# 2_waffling60-SI_matrix.net
KiCad netlist of a schematic drawn in Altium Designer
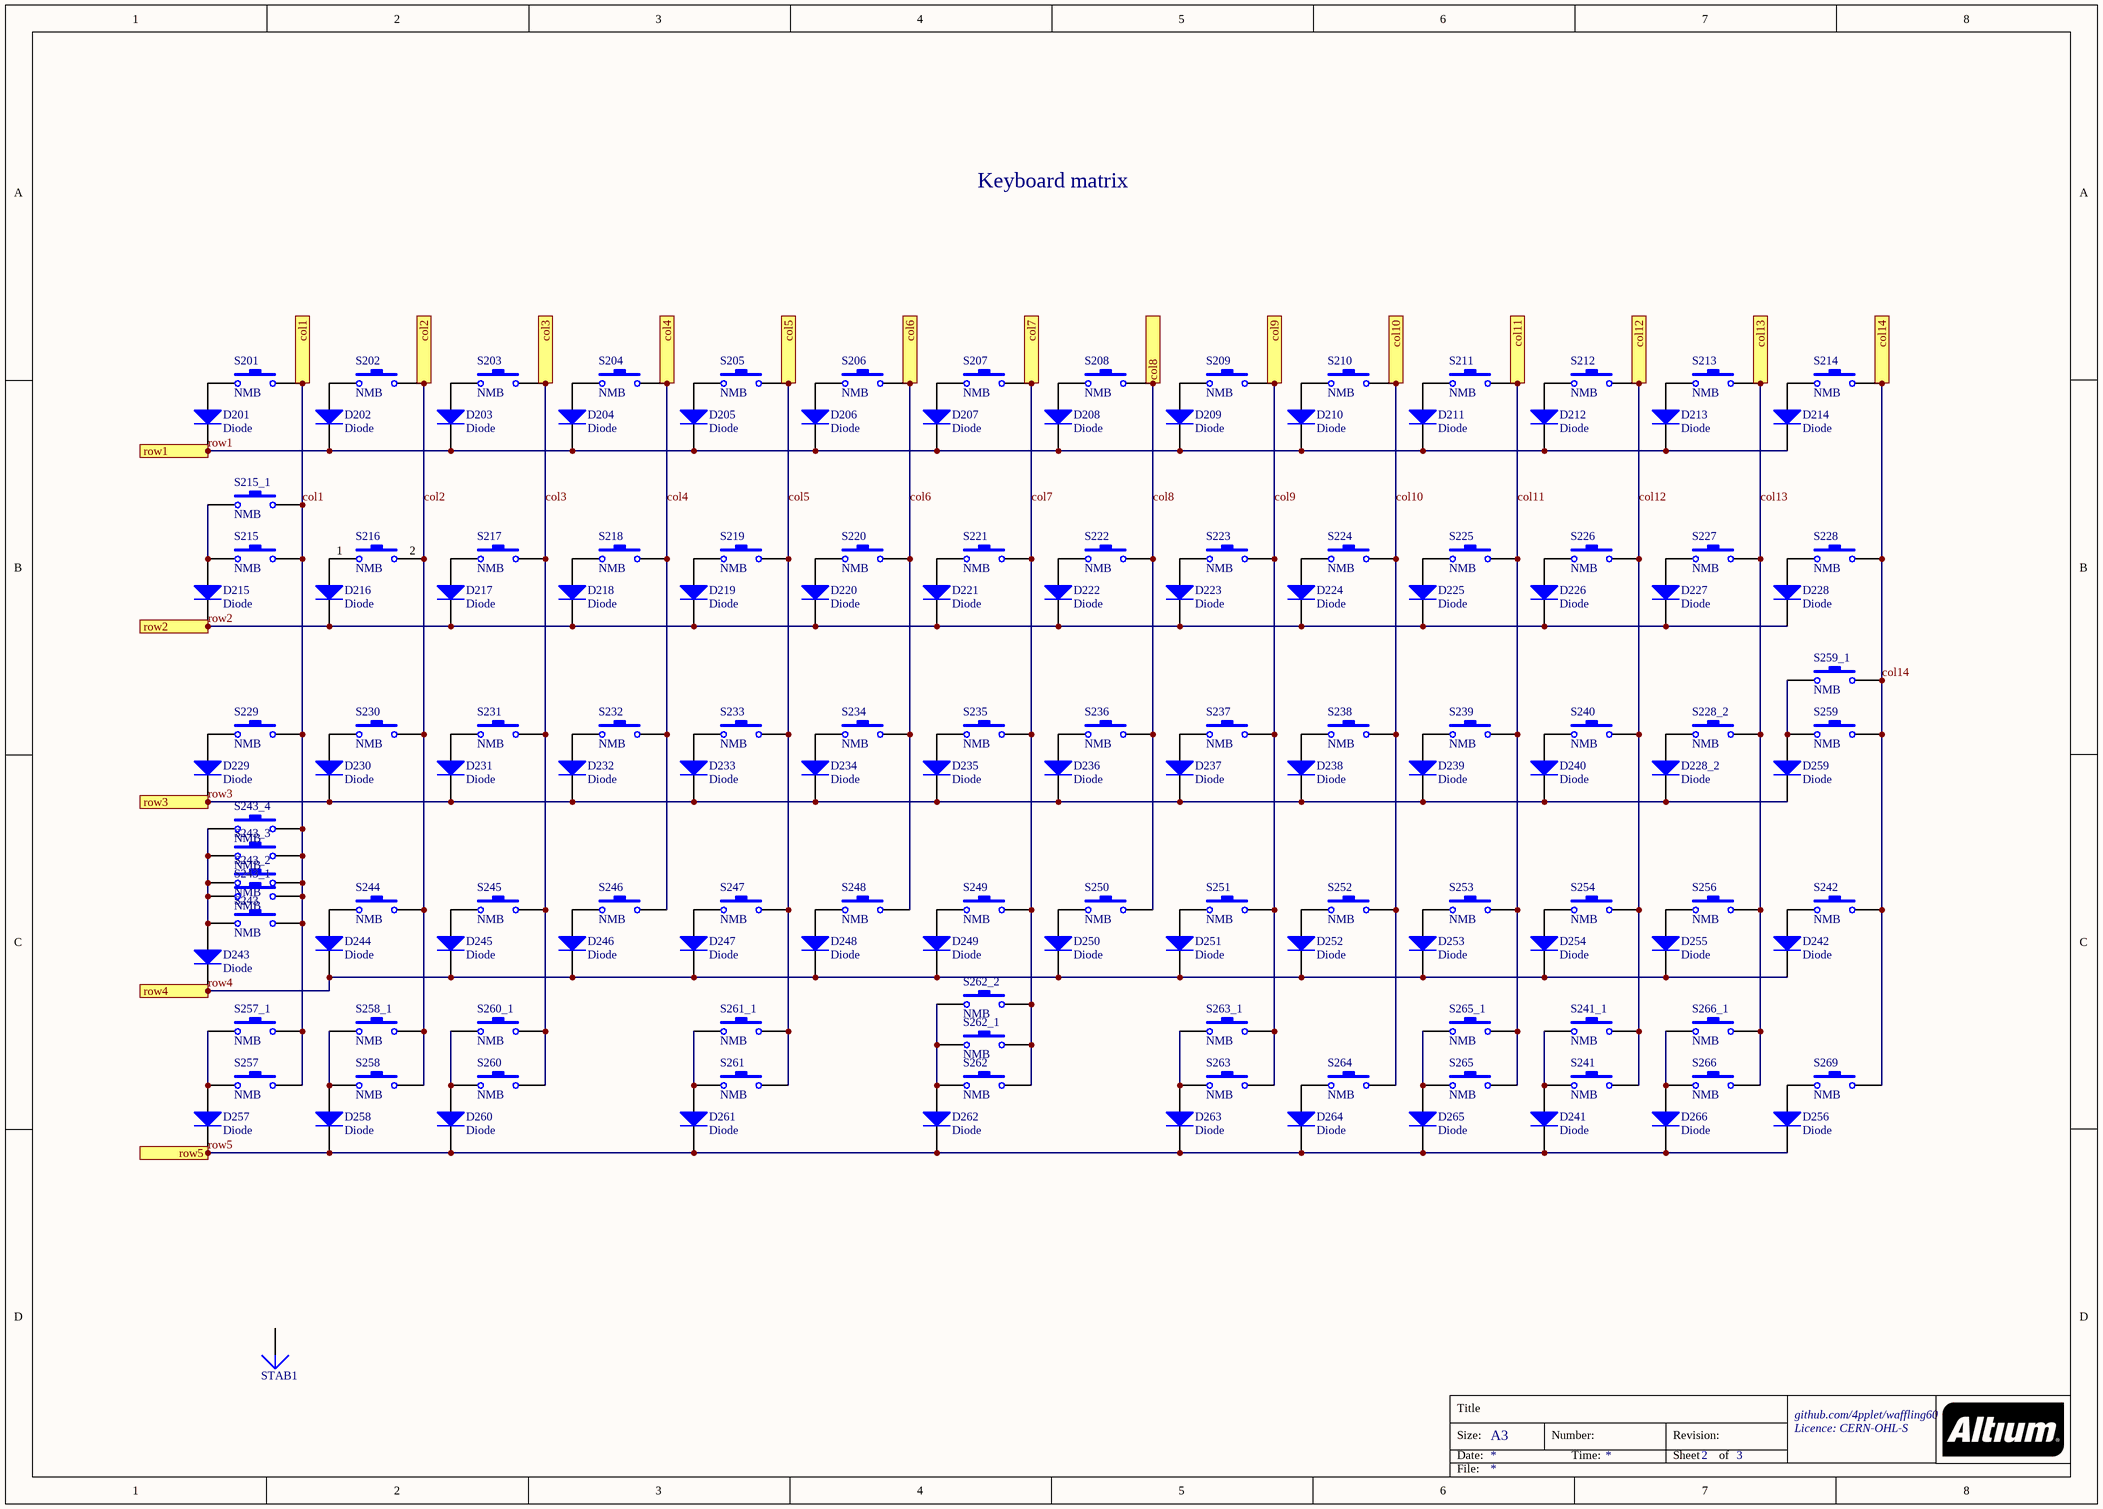
[diagram p0: 2_waffling60-SI_matrix.SchDoc]

(export (version "E")
  (design (tool "Eeschema 10.0.6"))
  (components
    (comp (ref "D201")
      (value "Diode")
      (footprint "SOD-123")
      (description "Default Diode")
      (fields (field (name "LCSC PART #") "C81598") (field (name "MRF.PART") "1N4148W"))
      (libsource (lib "Miscellaneous Devices") (part "Diode"))
    )
    (comp (ref "D202")
      (value "Diode")
      (footprint "SOD-123")
      (description "Default Diode")
      (fields (field (name "LCSC PART #") "C81598") (field (name "MRF.PART") "1N4148W"))
      (libsource (lib "Miscellaneous Devices") (part "Diode"))
    )
    (comp (ref "D203")
      (value "Diode")
      (footprint "SOD-123")
      (description "Default Diode")
      (fields (field (name "LCSC PART #") "C81598") (field (name "MRF.PART") "1N4148W"))
      (libsource (lib "Miscellaneous Devices") (part "Diode"))
    )
    (comp (ref "D204")
      (value "Diode")
      (footprint "SOD-123")
      (description "Default Diode")
      (fields (field (name "LCSC PART #") "C81598") (field (name "MRF.PART") "1N4148W"))
      (libsource (lib "Miscellaneous Devices") (part "Diode"))
    )
    (comp (ref "D205")
      (value "Diode")
      (footprint "SOD-123")
      (description "Default Diode")
      (fields (field (name "LCSC PART #") "C81598") (field (name "MRF.PART") "1N4148W"))
      (libsource (lib "Miscellaneous Devices") (part "Diode"))
    )
    (comp (ref "D206")
      (value "Diode")
      (footprint "SOD-123")
      (description "Default Diode")
      (fields (field (name "LCSC PART #") "C81598") (field (name "MRF.PART") "1N4148W"))
      (libsource (lib "Miscellaneous Devices") (part "Diode"))
    )
    (comp (ref "D207")
      (value "Diode")
      (footprint "SOD-123")
      (description "Default Diode")
      (fields (field (name "LCSC PART #") "C81598") (field (name "MRF.PART") "1N4148W"))
      (libsource (lib "Miscellaneous Devices") (part "Diode"))
    )
    (comp (ref "D208")
      (value "Diode")
      (footprint "SOD-123")
      (description "Default Diode")
      (fields (field (name "LCSC PART #") "C81598") (field (name "MRF.PART") "1N4148W"))
      (libsource (lib "Miscellaneous Devices") (part "Diode"))
    )
    (comp (ref "D209")
      (value "Diode")
      (footprint "SOD-123")
      (description "Default Diode")
      (fields (field (name "LCSC PART #") "C81598") (field (name "MRF.PART") "1N4148W"))
      (libsource (lib "Miscellaneous Devices") (part "Diode"))
    )
    (comp (ref "D210")
      (value "Diode")
      (footprint "SOD-123")
      (description "Default Diode")
      (fields (field (name "LCSC PART #") "C81598") (field (name "MRF.PART") "1N4148W"))
      (libsource (lib "Miscellaneous Devices") (part "Diode"))
    )
    (comp (ref "D211")
      (value "Diode")
      (footprint "SOD-123")
      (description "Default Diode")
      (fields (field (name "LCSC PART #") "C81598") (field (name "MRF.PART") "1N4148W"))
      (libsource (lib "Miscellaneous Devices") (part "Diode"))
    )
    (comp (ref "D212")
      (value "Diode")
      (footprint "SOD-123")
      (description "Default Diode")
      (fields (field (name "LCSC PART #") "C81598") (field (name "MRF.PART") "1N4148W"))
      (libsource (lib "Miscellaneous Devices") (part "Diode"))
    )
    (comp (ref "D213")
      (value "Diode")
      (footprint "SOD-123")
      (description "Default Diode")
      (fields (field (name "LCSC PART #") "C81598") (field (name "MRF.PART") "1N4148W"))
      (libsource (lib "Miscellaneous Devices") (part "Diode"))
    )
    (comp (ref "D214")
      (value "Diode")
      (footprint "SOD-123")
      (description "Default Diode")
      (fields (field (name "LCSC PART #") "C81598") (field (name "MRF.PART") "1N4148W"))
      (libsource (lib "Miscellaneous Devices") (part "Diode"))
    )
    (comp (ref "D215")
      (value "Diode")
      (footprint "SOD-123")
      (description "Default Diode")
      (fields (field (name "LCSC PART #") "C81598") (field (name "MRF.PART") "1N4148W"))
      (libsource (lib "Miscellaneous Devices") (part "Diode"))
    )
    (comp (ref "D216")
      (value "Diode")
      (footprint "SOD-123")
      (description "Default Diode")
      (fields (field (name "LCSC PART #") "C81598") (field (name "MRF.PART") "1N4148W"))
      (libsource (lib "Miscellaneous Devices") (part "Diode"))
    )
    (comp (ref "D217")
      (value "Diode")
      (footprint "SOD-123")
      (description "Default Diode")
      (fields (field (name "LCSC PART #") "C81598") (field (name "MRF.PART") "1N4148W"))
      (libsource (lib "Miscellaneous Devices") (part "Diode"))
    )
    (comp (ref "D218")
      (value "Diode")
      (footprint "SOD-123")
      (description "Default Diode")
      (fields (field (name "LCSC PART #") "C81598") (field (name "MRF.PART") "1N4148W"))
      (libsource (lib "Miscellaneous Devices") (part "Diode"))
    )
    (comp (ref "D219")
      (value "Diode")
      (footprint "SOD-123")
      (description "Default Diode")
      (fields (field (name "LCSC PART #") "C81598") (field (name "MRF.PART") "1N4148W"))
      (libsource (lib "Miscellaneous Devices") (part "Diode"))
    )
    (comp (ref "D220")
      (value "Diode")
      (footprint "SOD-123")
      (description "Default Diode")
      (fields (field (name "LCSC PART #") "C81598") (field (name "MRF.PART") "1N4148W"))
      (libsource (lib "Miscellaneous Devices") (part "Diode"))
    )
    (comp (ref "D221")
      (value "Diode")
      (footprint "SOD-123")
      (description "Default Diode")
      (fields (field (name "LCSC PART #") "C81598") (field (name "MRF.PART") "1N4148W"))
      (libsource (lib "Miscellaneous Devices") (part "Diode"))
    )
    (comp (ref "D222")
      (value "Diode")
      (footprint "SOD-123")
      (description "Default Diode")
      (fields (field (name "LCSC PART #") "C81598") (field (name "MRF.PART") "1N4148W"))
      (libsource (lib "Miscellaneous Devices") (part "Diode"))
    )
    (comp (ref "D223")
      (value "Diode")
      (footprint "SOD-123")
      (description "Default Diode")
      (fields (field (name "LCSC PART #") "C81598") (field (name "MRF.PART") "1N4148W"))
      (libsource (lib "Miscellaneous Devices") (part "Diode"))
    )
    (comp (ref "D224")
      (value "Diode")
      (footprint "SOD-123")
      (description "Default Diode")
      (fields (field (name "LCSC PART #") "C81598") (field (name "MRF.PART") "1N4148W"))
      (libsource (lib "Miscellaneous Devices") (part "Diode"))
    )
    (comp (ref "D225")
      (value "Diode")
      (footprint "SOD-123")
      (description "Default Diode")
      (fields (field (name "LCSC PART #") "C81598") (field (name "MRF.PART") "1N4148W"))
      (libsource (lib "Miscellaneous Devices") (part "Diode"))
    )
    (comp (ref "D226")
      (value "Diode")
      (footprint "SOD-123")
      (description "Default Diode")
      (fields (field (name "LCSC PART #") "C81598") (field (name "MRF.PART") "1N4148W"))
      (libsource (lib "Miscellaneous Devices") (part "Diode"))
    )
    (comp (ref "D227")
      (value "Diode")
      (footprint "SOD-123")
      (description "Default Diode")
      (fields (field (name "LCSC PART #") "C81598") (field (name "MRF.PART") "1N4148W"))
      (libsource (lib "Miscellaneous Devices") (part "Diode"))
    )
    (comp (ref "D228")
      (value "Diode")
      (footprint "SOD-123")
      (description "Default Diode")
      (fields (field (name "LCSC PART #") "C81598") (field (name "MRF.PART") "1N4148W"))
      (libsource (lib "Miscellaneous Devices") (part "Diode"))
    )
    (comp (ref "D228_2")
      (value "Diode")
      (footprint "SOD-123")
      (description "Default Diode")
      (fields (field (name "LCSC PART #") "C81598") (field (name "MRF.PART") "1N4148W"))
      (libsource (lib "Miscellaneous Devices") (part "Diode"))
    )
    (comp (ref "D229")
      (value "Diode")
      (footprint "SOD-123")
      (description "Default Diode")
      (fields (field (name "LCSC PART #") "C81598") (field (name "MRF.PART") "1N4148W"))
      (libsource (lib "Miscellaneous Devices") (part "Diode"))
    )
    (comp (ref "D230")
      (value "Diode")
      (footprint "SOD-123")
      (description "Default Diode")
      (fields (field (name "LCSC PART #") "C81598") (field (name "MRF.PART") "1N4148W"))
      (libsource (lib "Miscellaneous Devices") (part "Diode"))
    )
    (comp (ref "D231")
      (value "Diode")
      (footprint "SOD-123")
      (description "Default Diode")
      (fields (field (name "LCSC PART #") "C81598") (field (name "MRF.PART") "1N4148W"))
      (libsource (lib "Miscellaneous Devices") (part "Diode"))
    )
    (comp (ref "D232")
      (value "Diode")
      (footprint "SOD-123")
      (description "Default Diode")
      (fields (field (name "LCSC PART #") "C81598") (field (name "MRF.PART") "1N4148W"))
      (libsource (lib "Miscellaneous Devices") (part "Diode"))
    )
    (comp (ref "D233")
      (value "Diode")
      (footprint "SOD-123")
      (description "Default Diode")
      (fields (field (name "LCSC PART #") "C81598") (field (name "MRF.PART") "1N4148W"))
      (libsource (lib "Miscellaneous Devices") (part "Diode"))
    )
    (comp (ref "D234")
      (value "Diode")
      (footprint "SOD-123")
      (description "Default Diode")
      (fields (field (name "LCSC PART #") "C81598") (field (name "MRF.PART") "1N4148W"))
      (libsource (lib "Miscellaneous Devices") (part "Diode"))
    )
    (comp (ref "D235")
      (value "Diode")
      (footprint "SOD-123")
      (description "Default Diode")
      (fields (field (name "LCSC PART #") "C81598") (field (name "MRF.PART") "1N4148W"))
      (libsource (lib "Miscellaneous Devices") (part "Diode"))
    )
    (comp (ref "D236")
      (value "Diode")
      (footprint "SOD-123")
      (description "Default Diode")
      (fields (field (name "LCSC PART #") "C81598") (field (name "MRF.PART") "1N4148W"))
      (libsource (lib "Miscellaneous Devices") (part "Diode"))
    )
    (comp (ref "D237")
      (value "Diode")
      (footprint "SOD-123")
      (description "Default Diode")
      (fields (field (name "LCSC PART #") "C81598") (field (name "MRF.PART") "1N4148W"))
      (libsource (lib "Miscellaneous Devices") (part "Diode"))
    )
    (comp (ref "D238")
      (value "Diode")
      (footprint "SOD-123")
      (description "Default Diode")
      (fields (field (name "LCSC PART #") "C81598") (field (name "MRF.PART") "1N4148W"))
      (libsource (lib "Miscellaneous Devices") (part "Diode"))
    )
    (comp (ref "D239")
      (value "Diode")
      (footprint "SOD-123")
      (description "Default Diode")
      (fields (field (name "LCSC PART #") "C81598") (field (name "MRF.PART") "1N4148W"))
      (libsource (lib "Miscellaneous Devices") (part "Diode"))
    )
    (comp (ref "D240")
      (value "Diode")
      (footprint "SOD-123")
      (description "Default Diode")
      (fields (field (name "LCSC PART #") "C81598") (field (name "MRF.PART") "1N4148W"))
      (libsource (lib "Miscellaneous Devices") (part "Diode"))
    )
    (comp (ref "D241")
      (value "Diode")
      (footprint "SOD-123")
      (description "Default Diode")
      (fields (field (name "LCSC PART #") "C81598") (field (name "MRF.PART") "1N4148W"))
      (libsource (lib "Miscellaneous Devices") (part "Diode"))
    )
    (comp (ref "D242")
      (value "Diode")
      (footprint "SOD-123")
      (description "Default Diode")
      (fields (field (name "LCSC PART #") "C81598") (field (name "MRF.PART") "1N4148W"))
      (libsource (lib "Miscellaneous Devices") (part "Diode"))
    )
    (comp (ref "D243")
      (value "Diode")
      (footprint "SOD-123")
      (description "Default Diode")
      (fields (field (name "LCSC PART #") "C81598") (field (name "MRF.PART") "1N4148W"))
      (libsource (lib "Miscellaneous Devices") (part "Diode"))
    )
    (comp (ref "D244")
      (value "Diode")
      (footprint "SOD-123")
      (description "Default Diode")
      (fields (field (name "LCSC PART #") "C81598") (field (name "MRF.PART") "1N4148W"))
      (libsource (lib "Miscellaneous Devices") (part "Diode"))
    )
    (comp (ref "D245")
      (value "Diode")
      (footprint "SOD-123")
      (description "Default Diode")
      (fields (field (name "LCSC PART #") "C81598") (field (name "MRF.PART") "1N4148W"))
      (libsource (lib "Miscellaneous Devices") (part "Diode"))
    )
    (comp (ref "D246")
      (value "Diode")
      (footprint "SOD-123")
      (description "Default Diode")
      (fields (field (name "LCSC PART #") "C81598") (field (name "MRF.PART") "1N4148W"))
      (libsource (lib "Miscellaneous Devices") (part "Diode"))
    )
    (comp (ref "D247")
      (value "Diode")
      (footprint "SOD-123")
      (description "Default Diode")
      (fields (field (name "LCSC PART #") "C81598") (field (name "MRF.PART") "1N4148W"))
      (libsource (lib "Miscellaneous Devices") (part "Diode"))
    )
    (comp (ref "D248")
      (value "Diode")
      (footprint "SOD-123")
      (description "Default Diode")
      (fields (field (name "LCSC PART #") "C81598") (field (name "MRF.PART") "1N4148W"))
      (libsource (lib "Miscellaneous Devices") (part "Diode"))
    )
    (comp (ref "D249")
      (value "Diode")
      (footprint "SOD-123")
      (description "Default Diode")
      (fields (field (name "LCSC PART #") "C81598") (field (name "MRF.PART") "1N4148W"))
      (libsource (lib "Miscellaneous Devices") (part "Diode"))
    )
    (comp (ref "D250")
      (value "Diode")
      (footprint "SOD-123")
      (description "Default Diode")
      (fields (field (name "LCSC PART #") "C81598") (field (name "MRF.PART") "1N4148W"))
      (libsource (lib "Miscellaneous Devices") (part "Diode"))
    )
    (comp (ref "D251")
      (value "Diode")
      (footprint "SOD-123")
      (description "Default Diode")
      (fields (field (name "LCSC PART #") "C81598") (field (name "MRF.PART") "1N4148W"))
      (libsource (lib "Miscellaneous Devices") (part "Diode"))
    )
    (comp (ref "D252")
      (value "Diode")
      (footprint "SOD-123")
      (description "Default Diode")
      (fields (field (name "LCSC PART #") "C81598") (field (name "MRF.PART") "1N4148W"))
      (libsource (lib "Miscellaneous Devices") (part "Diode"))
    )
    (comp (ref "D253")
      (value "Diode")
      (footprint "SOD-123")
      (description "Default Diode")
      (fields (field (name "LCSC PART #") "C81598") (field (name "MRF.PART") "1N4148W"))
      (libsource (lib "Miscellaneous Devices") (part "Diode"))
    )
    (comp (ref "D254")
      (value "Diode")
      (footprint "SOD-123")
      (description "Default Diode")
      (fields (field (name "LCSC PART #") "C81598") (field (name "MRF.PART") "1N4148W"))
      (libsource (lib "Miscellaneous Devices") (part "Diode"))
    )
    (comp (ref "D255")
      (value "Diode")
      (footprint "SOD-123")
      (description "Default Diode")
      (fields (field (name "LCSC PART #") "C81598") (field (name "MRF.PART") "1N4148W"))
      (libsource (lib "Miscellaneous Devices") (part "Diode"))
    )
    (comp (ref "D256")
      (value "Diode")
      (footprint "SOD-123")
      (description "Default Diode")
      (fields (field (name "LCSC PART #") "C81598") (field (name "MRF.PART") "1N4148W"))
      (libsource (lib "Miscellaneous Devices") (part "Diode"))
    )
    (comp (ref "D257")
      (value "Diode")
      (footprint "SOD-123")
      (description "Default Diode")
      (fields (field (name "LCSC PART #") "C81598") (field (name "MRF.PART") "1N4148W"))
      (libsource (lib "Miscellaneous Devices") (part "Diode"))
    )
    (comp (ref "D258")
      (value "Diode")
      (footprint "SOD-123")
      (description "Default Diode")
      (fields (field (name "LCSC PART #") "C81598") (field (name "MRF.PART") "1N4148W"))
      (libsource (lib "Miscellaneous Devices") (part "Diode"))
    )
    (comp (ref "D259")
      (value "Diode")
      (footprint "SOD-123")
      (description "Default Diode")
      (fields (field (name "LCSC PART #") "C81598") (field (name "MRF.PART") "1N4148W"))
      (libsource (lib "Miscellaneous Devices") (part "Diode"))
    )
    (comp (ref "D260")
      (value "Diode")
      (footprint "SOD-123")
      (description "Default Diode")
      (fields (field (name "LCSC PART #") "C81598") (field (name "MRF.PART") "1N4148W"))
      (libsource (lib "Miscellaneous Devices") (part "Diode"))
    )
    (comp (ref "D261")
      (value "Diode")
      (footprint "SOD-123")
      (description "Default Diode")
      (fields (field (name "LCSC PART #") "C81598") (field (name "MRF.PART") "1N4148W"))
      (libsource (lib "Miscellaneous Devices") (part "Diode"))
    )
    (comp (ref "D262")
      (value "Diode")
      (footprint "SOD-123")
      (description "Default Diode")
      (fields (field (name "LCSC PART #") "C81598") (field (name "MRF.PART") "1N4148W"))
      (libsource (lib "Miscellaneous Devices") (part "Diode"))
    )
    (comp (ref "D263")
      (value "Diode")
      (footprint "SOD-123")
      (description "Default Diode")
      (fields (field (name "LCSC PART #") "C81598") (field (name "MRF.PART") "1N4148W"))
      (libsource (lib "Miscellaneous Devices") (part "Diode"))
    )
    (comp (ref "D264")
      (value "Diode")
      (footprint "SOD-123")
      (description "Default Diode")
      (fields (field (name "LCSC PART #") "C81598") (field (name "MRF.PART") "1N4148W"))
      (libsource (lib "Miscellaneous Devices") (part "Diode"))
    )
    (comp (ref "D265")
      (value "Diode")
      (footprint "SOD-123")
      (description "Default Diode")
      (fields (field (name "LCSC PART #") "C81598") (field (name "MRF.PART") "1N4148W"))
      (libsource (lib "Miscellaneous Devices") (part "Diode"))
    )
    (comp (ref "D266")
      (value "Diode")
      (footprint "SOD-123")
      (description "Default Diode")
      (fields (field (name "LCSC PART #") "C81598") (field (name "MRF.PART") "1N4148W"))
      (libsource (lib "Miscellaneous Devices") (part "Diode"))
    )
    (comp (ref "S201")
      (value "NMB")
      (footprint "NMB-Switch 1U - switched pol  - no allignment pins")
      (description "Switch")
      (libsource (lib "Miscellaneous Devices") (part "SW-PB"))
    )
    (comp (ref "S202")
      (value "NMB")
      (footprint "NMB-Switch 1U - no allignment pins")
      (description "Switch")
      (libsource (lib "Miscellaneous Devices") (part "SW-PB"))
    )
    (comp (ref "S203")
      (value "NMB")
      (footprint "NMB-Switch 1U - switched pol  - no allignment pins")
      (description "Switch")
      (libsource (lib "Miscellaneous Devices") (part "SW-PB"))
    )
    (comp (ref "S204")
      (value "NMB")
      (footprint "NMB-Switch 1U - switched pol  - no allignment pins")
      (description "Switch")
      (libsource (lib "Miscellaneous Devices") (part "SW-PB"))
    )
    (comp (ref "S205")
      (value "NMB")
      (footprint "NMB-Switch 1U - switched pol  - no allignment pins")
      (description "Switch")
      (libsource (lib "Miscellaneous Devices") (part "SW-PB"))
    )
    (comp (ref "S206")
      (value "NMB")
      (footprint "NMB-Switch 1U - switched pol  - no allignment pins")
      (description "Switch")
      (libsource (lib "Miscellaneous Devices") (part "SW-PB"))
    )
    (comp (ref "S207")
      (value "NMB")
      (footprint "NMB-Switch 1U - switched pol  - no allignment pins")
      (description "Switch")
      (libsource (lib "Miscellaneous Devices") (part "SW-PB"))
    )
    (comp (ref "S208")
      (value "NMB")
      (footprint "NMB-Switch 1U - switched pol  - no allignment pins")
      (description "Switch")
      (libsource (lib "Miscellaneous Devices") (part "SW-PB"))
    )
    (comp (ref "S209")
      (value "NMB")
      (footprint "NMB-Switch 1U - switched pol  - no allignment pins")
      (description "Switch")
      (libsource (lib "Miscellaneous Devices") (part "SW-PB"))
    )
    (comp (ref "S210")
      (value "NMB")
      (footprint "NMB-Switch 1U - switched pol  - no allignment pins")
      (description "Switch")
      (libsource (lib "Miscellaneous Devices") (part "SW-PB"))
    )
    (comp (ref "S211")
      (value "NMB")
      (footprint "NMB-Switch 1U - switched pol  - no allignment pins")
      (description "Switch")
      (libsource (lib "Miscellaneous Devices") (part "SW-PB"))
    )
    (comp (ref "S212")
      (value "NMB")
      (footprint "NMB-Switch 1U - switched pol  - no allignment pins")
      (description "Switch")
      (libsource (lib "Miscellaneous Devices") (part "SW-PB"))
    )
    (comp (ref "S213")
      (value "NMB")
      (footprint "NMB-Switch 1U - switched pol  - no allignment pins")
      (description "Switch")
      (libsource (lib "Miscellaneous Devices") (part "SW-PB"))
    )
    (comp (ref "S214")
      (value "NMB")
      (footprint "NMB-Switch 1U - no allignment pins")
      (description "Switch")
      (libsource (lib "Miscellaneous Devices") (part "SW-PB"))
    )
    (comp (ref "S215")
      (value "NMB")
      (footprint "NMB-Switch 1U - switched pol  - no allignment pins")
      (description "TAB")
      (libsource (lib "Miscellaneous Devices") (part "SW-PB"))
    )
    (comp (ref "S215_1")
      (value "NMB")
      (footprint "NMB-Switch 1U - switched pol  - no allignment pins")
      (description "TAB")
      (libsource (lib "Miscellaneous Devices") (part "SW-PB"))
    )
    (comp (ref "S216")
      (value "NMB")
      (footprint "NMB-Switch 1U - no allignment pins")
      (description "Switch")
      (libsource (lib "") (part "SW-PB_1"))
    )
    (comp (ref "S217")
      (value "NMB")
      (footprint "NMB-Switch 1U - switched pol  - no allignment pins")
      (description "Switch")
      (libsource (lib "Miscellaneous Devices") (part "SW-PB"))
    )
    (comp (ref "S218")
      (value "NMB")
      (footprint "NMB-Switch 1U - switched pol  - no allignment pins")
      (description "Switch")
      (libsource (lib "Miscellaneous Devices") (part "SW-PB"))
    )
    (comp (ref "S219")
      (value "NMB")
      (footprint "NMB-Switch 1U - switched pol  - no allignment pins")
      (description "Switch")
      (libsource (lib "Miscellaneous Devices") (part "SW-PB"))
    )
    (comp (ref "S220")
      (value "NMB")
      (footprint "NMB-Switch 1U - no allignment pins")
      (description "Switch")
      (libsource (lib "Miscellaneous Devices") (part "SW-PB"))
    )
    (comp (ref "S221")
      (value "NMB")
      (footprint "NMB-Switch 1U - switched pol  - no allignment pins")
      (description "Switch")
      (libsource (lib "Miscellaneous Devices") (part "SW-PB"))
    )
    (comp (ref "S222")
      (value "NMB")
      (footprint "NMB-Switch 1U - no allignment pins")
      (description "Switch")
      (libsource (lib "Miscellaneous Devices") (part "SW-PB"))
    )
    (comp (ref "S223")
      (value "NMB")
      (footprint "NMB-Switch 1U - switched pol  - no allignment pins")
      (description "Switch")
      (libsource (lib "Miscellaneous Devices") (part "SW-PB"))
    )
    (comp (ref "S224")
      (value "NMB")
      (footprint "NMB-Switch 1U - switched pol  - no allignment pins")
      (description "Switch")
      (libsource (lib "Miscellaneous Devices") (part "SW-PB"))
    )
    (comp (ref "S225")
      (value "NMB")
      (footprint "NMB-Switch 1U - switched pol  - no allignment pins")
      (description "Switch")
      (libsource (lib "Miscellaneous Devices") (part "SW-PB"))
    )
    (comp (ref "S226")
      (value "NMB")
      (footprint "NMB-Switch 1U - no allignment pins")
      (description "Switch")
      (libsource (lib "Miscellaneous Devices") (part "SW-PB"))
    )
    (comp (ref "S227")
      (value "NMB")
      (footprint "NMB-Switch 1U - no allignment pins")
      (description "Switch")
      (libsource (lib "Miscellaneous Devices") (part "SW-PB"))
    )
    (comp (ref "S228")
      (value "NMB")
      (footprint "NMB-Switch 1U - no allignment pins")
      (description "Switch")
      (libsource (lib "Miscellaneous Devices") (part "SW-PB"))
    )
    (comp (ref "S228_2")
      (value "NMB")
      (footprint "NMB-Switch 1U - no allignment pins")
      (description "Switch")
      (libsource (lib "Miscellaneous Devices") (part "SW-PB"))
    )
    (comp (ref "S229")
      (value "NMB")
      (footprint "NMB-Switch 1U - no allignment pins")
      (description "Switch")
      (libsource (lib "Miscellaneous Devices") (part "SW-PB"))
    )
    (comp (ref "S230")
      (value "NMB")
      (footprint "NMB-Switch 1U - no allignment pins")
      (description "Switch")
      (libsource (lib "Miscellaneous Devices") (part "SW-PB"))
    )
    (comp (ref "S231")
      (value "NMB")
      (footprint "NMB-Switch 1U - switched pol  - no allignment pins")
      (description "Switch")
      (libsource (lib "Miscellaneous Devices") (part "SW-PB"))
    )
    (comp (ref "S232")
      (value "NMB")
      (footprint "NMB-Switch 1U - switched pol  - no allignment pins")
      (description "Switch")
      (libsource (lib "Miscellaneous Devices") (part "SW-PB"))
    )
    (comp (ref "S233")
      (value "NMB")
      (footprint "NMB-Switch 1U - switched pol  - no allignment pins")
      (description "Switch")
      (libsource (lib "Miscellaneous Devices") (part "SW-PB"))
    )
    (comp (ref "S234")
      (value "NMB")
      (footprint "NMB-Switch 1U - switched pol  - no allignment pins")
      (description "Switch")
      (libsource (lib "Miscellaneous Devices") (part "SW-PB"))
    )
    (comp (ref "S235")
      (value "NMB")
      (footprint "NMB-Switch 1U - switched pol  - no allignment pins")
      (description "Switch")
      (libsource (lib "Miscellaneous Devices") (part "SW-PB"))
    )
    (comp (ref "S236")
      (value "NMB")
      (footprint "NMB-Switch 1U - switched pol  - no allignment pins")
      (description "Switch")
      (libsource (lib "Miscellaneous Devices") (part "SW-PB"))
    )
    (comp (ref "S237")
      (value "NMB")
      (footprint "NMB-Switch 1U - switched pol  - no allignment pins")
      (description "Switch")
      (libsource (lib "Miscellaneous Devices") (part "SW-PB"))
    )
    (comp (ref "S238")
      (value "NMB")
      (footprint "NMB-Switch 1U - switched pol  - no allignment pins")
      (description "Switch")
      (libsource (lib "Miscellaneous Devices") (part "SW-PB"))
    )
    (comp (ref "S239")
      (value "NMB")
      (footprint "NMB-Switch 1U - switched pol  - no allignment pins")
      (description "Switch")
      (libsource (lib "Miscellaneous Devices") (part "SW-PB"))
    )
    (comp (ref "S240")
      (value "NMB")
      (footprint "NMB-Switch 1U - switched pol  - no allignment pins")
      (description "Switch")
      (libsource (lib "Miscellaneous Devices") (part "SW-PB"))
    )
    (comp (ref "S241")
      (value "NMB")
      (footprint "NMB-Switch 1U - no allignment pins")
      (description "Switch")
      (libsource (lib "Miscellaneous Devices") (part "SW-PB"))
    )
    (comp (ref "S241_1")
      (value "NMB")
      (footprint "NMB-Switch 1U - no allignment pins")
      (description "Switch")
      (libsource (lib "Miscellaneous Devices") (part "SW-PB"))
    )
    (comp (ref "S242")
      (value "NMB")
      (footprint "MX-switch - Enter - Rotated Stab")
      (description "Switch")
      (libsource (lib "Miscellaneous Devices") (part "SW-PB"))
    )
    (comp (ref "S243")
      (value "NMB")
      (footprint "MX-switch - Left shift")
      (description "Switch")
      (libsource (lib "Miscellaneous Devices") (part "SW-PB"))
    )
    (comp (ref "S243_1")
      (value "NMB")
      (footprint "MX-switch - Left shift")
      (description "Switch")
      (libsource (lib "Miscellaneous Devices") (part "SW-PB"))
    )
    (comp (ref "S243_2")
      (value "NMB")
      (footprint "MX-switch - Left shift")
      (description "Switch")
      (libsource (lib "Miscellaneous Devices") (part "SW-PB"))
    )
    (comp (ref "S243_3")
      (value "NMB")
      (footprint "MX-switch - Left shift")
      (description "Switch")
      (libsource (lib "Miscellaneous Devices") (part "SW-PB"))
    )
    (comp (ref "S243_4")
      (value "NMB")
      (footprint "MX-switch - Left shift")
      (description "Switch")
      (libsource (lib "Miscellaneous Devices") (part "SW-PB"))
    )
    (comp (ref "S244")
      (value "NMB")
      (footprint "NMB-Switch 1U - no allignment pins")
      (description "Switch")
      (libsource (lib "Miscellaneous Devices") (part "SW-PB"))
    )
    (comp (ref "S245")
      (value "NMB")
      (footprint "NMB-Switch 1U - switched pol  - no allignment pins")
      (description "Switch")
      (libsource (lib "Miscellaneous Devices") (part "SW-PB"))
    )
    (comp (ref "S246")
      (value "NMB")
      (footprint "NMB-Switch 1U - switched pol  - no allignment pins")
      (description "Switch")
      (libsource (lib "Miscellaneous Devices") (part "SW-PB"))
    )
    (comp (ref "S247")
      (value "NMB")
      (footprint "NMB-Switch 1U - switched pol  - no allignment pins")
      (description "Switch")
      (libsource (lib "Miscellaneous Devices") (part "SW-PB"))
    )
    (comp (ref "S248")
      (value "NMB")
      (footprint "NMB-Switch 1U - switched pol  - no allignment pins")
      (description "Switch")
      (libsource (lib "Miscellaneous Devices") (part "SW-PB"))
    )
    (comp (ref "S249")
      (value "NMB")
      (footprint "NMB-Switch 1U - switched pol  - no allignment pins")
      (description "Switch")
      (libsource (lib "Miscellaneous Devices") (part "SW-PB"))
    )
    (comp (ref "S250")
      (value "NMB")
      (footprint "NMB-Switch 1U - switched pol  - no allignment pins")
      (description "Switch")
      (libsource (lib "Miscellaneous Devices") (part "SW-PB"))
    )
    (comp (ref "S251")
      (value "NMB")
      (footprint "NMB-Switch 1U - switched pol  - no allignment pins")
      (description "Switch")
      (libsource (lib "Miscellaneous Devices") (part "SW-PB"))
    )
    (comp (ref "S252")
      (value "NMB")
      (footprint "NMB-Switch 1U - switched pol  - no allignment pins")
      (description "Switch")
      (libsource (lib "Miscellaneous Devices") (part "SW-PB"))
    )
    (comp (ref "S253")
      (value "NMB")
      (footprint "NMB-Switch 1U - switched pol  - no allignment pins")
      (description "Switch")
      (libsource (lib "Miscellaneous Devices") (part "SW-PB"))
    )
    (comp (ref "S254")
      (value "NMB")
      (footprint "NMB-Switch 1U - switched pol  - no allignment pins")
      (description "Switch")
      (libsource (lib "Miscellaneous Devices") (part "SW-PB"))
    )
    (comp (ref "S256")
      (value "NMB")
      (footprint "MX-switch - right shift")
      (description "Switch")
      (libsource (lib "Miscellaneous Devices") (part "SW-PB"))
    )
    (comp (ref "S257")
      (value "NMB")
      (footprint "NMB-Switch 1U - no allignment pins")
      (description "Switch")
      (libsource (lib "Miscellaneous Devices") (part "SW-PB"))
    )
    (comp (ref "S257_1")
      (value "NMB")
      (footprint "NMB-Switch 1U - no allignment pins")
      (description "Switch")
      (libsource (lib "Miscellaneous Devices") (part "SW-PB"))
    )
    (comp (ref "S258")
      (value "NMB")
      (footprint "NMB-Switch 1U - no allignment pins")
      (description "Switch")
      (libsource (lib "Miscellaneous Devices") (part "SW-PB"))
    )
    (comp (ref "S258_1")
      (value "NMB")
      (footprint "NMB-Switch 1U - no allignment pins")
      (description "Switch")
      (libsource (lib "Miscellaneous Devices") (part "SW-PB"))
    )
    (comp (ref "S259")
      (value "NMB")
      (footprint "NMB-Switch 1U - no allignment pins")
      (description "Switch")
      (libsource (lib "") (part "SW-PB_2"))
    )
    (comp (ref "S259_1")
      (value "NMB")
      (footprint "NMB-Switch 1U - no allignment pins")
      (description "Switch")
      (libsource (lib "Miscellaneous Devices") (part "SW-PB"))
    )
    (comp (ref "S260")
      (value "NMB")
      (footprint "NMB-Switch 1U - no allignment pins")
      (description "Switch")
      (libsource (lib "Miscellaneous Devices") (part "SW-PB"))
    )
    (comp (ref "S260_1")
      (value "NMB")
      (footprint "NMB-Switch 1U - no allignment pins")
      (description "Switch")
      (libsource (lib "Miscellaneous Devices") (part "SW-PB"))
    )
    (comp (ref "S261")
      (value "NMB")
      (footprint "MX-SWITCH - L SPLIT SPACE_V2")
      (description "Switch")
      (libsource (lib "Miscellaneous Devices") (part "SW-PB"))
    )
    (comp (ref "S261_1")
      (value "NMB")
      (footprint "MX-switch - 3U - rotated stab")
      (description "Switch")
      (libsource (lib "Miscellaneous Devices") (part "SW-PB"))
    )
    (comp (ref "S262")
      (value "NMB")
      (footprint "MX-switch - Space_V3")
      (description "Switch")
      (libsource (lib "Miscellaneous Devices") (part "SW-PB"))
    )
    (comp (ref "S262_1")
      (value "NMB")
      (footprint "MX-switch - 3U - rotated stab")
      (description "Switch")
      (libsource (lib "Miscellaneous Devices") (part "SW-PB"))
    )
    (comp (ref "S262_2")
      (value "NMB")
      (footprint "MX-switch - 3U - rotated stab")
      (description "Switch")
      (libsource (lib "Miscellaneous Devices") (part "SW-PB"))
    )
    (comp (ref "S263")
      (value "NMB")
      (footprint "MX-SWITCH - R SPLIT SPACE_V2")
      (description "Switch")
      (libsource (lib "Miscellaneous Devices") (part "SW-PB"))
    )
    (comp (ref "S263_1")
      (value "NMB")
      (footprint "MX-switch - 3U - rotated stab")
      (description "Switch")
      (libsource (lib "Miscellaneous Devices") (part "SW-PB"))
    )
    (comp (ref "S264")
      (value "NMB")
      (footprint "NMB-Switch 1U - switched pol  - no allignment pins")
      (description "Switch")
      (libsource (lib "Miscellaneous Devices") (part "SW-PB"))
    )
    (comp (ref "S265")
      (value "NMB")
      (footprint "NMB-Switch 1U - no allignment pins")
      (description "Switch")
      (libsource (lib "Miscellaneous Devices") (part "SW-PB"))
    )
    (comp (ref "S265_1")
      (value "NMB")
      (footprint "NMB-Switch 1U - no allignment pins")
      (description "Switch")
      (libsource (lib "Miscellaneous Devices") (part "SW-PB"))
    )
    (comp (ref "S266")
      (value "NMB")
      (footprint "NMB-Switch 1U - no allignment pins")
      (description "Switch")
      (libsource (lib "Miscellaneous Devices") (part "SW-PB"))
    )
    (comp (ref "S266_1")
      (value "NMB")
      (footprint "NMB-Switch 1U - no allignment pins")
      (description "Switch")
      (libsource (lib "Miscellaneous Devices") (part "SW-PB"))
    )
    (comp (ref "S269")
      (value "NMB")
      (footprint "NMB-Switch 1U - no allignment pins")
      (description "Switch")
      (libsource (lib "Miscellaneous Devices") (part "SW-PB"))
    )
    (comp (ref "STAB1")
      (value "Plug")
      (footprint "Stab 10U")
      (libsource (lib "Miscellaneous Connectors") (part "Plug"))
    )
  )
  (nets
    (net (code "1") (name "/col1") (class "Default")
      (node (ref "S201") (pin "2") (pinfunction "2_2") (pintype "passive"))
      (node (ref "S215") (pin "2") (pinfunction "2_2") (pintype "passive"))
      (node (ref "S215_1") (pin "2") (pinfunction "2_2") (pintype "passive"))
      (node (ref "S229") (pin "1") (pinfunction "1_1") (pintype "passive"))
      (node (ref "S243") (pin "2") (pinfunction "2_2") (pintype "passive"))
      (node (ref "S243_1") (pin "2") (pinfunction "2_2") (pintype "passive"))
      (node (ref "S243_2") (pin "2") (pinfunction "2_2") (pintype "passive"))
      (node (ref "S243_3") (pin "2") (pinfunction "2_2") (pintype "passive"))
      (node (ref "S243_4") (pin "2") (pinfunction "2_2") (pintype "passive"))
      (node (ref "S257") (pin "1") (pinfunction "1_1") (pintype "passive"))
      (node (ref "S257_1") (pin "1") (pinfunction "1_1") (pintype "passive"))
    )
    (net (code "2") (name "/col2") (class "Default")
      (node (ref "S202") (pin "2") (pinfunction "2_2") (pintype "passive"))
      (node (ref "S216") (pin "2") (pinfunction "2_2") (pintype "passive"))
      (node (ref "S230") (pin "2") (pinfunction "2_2") (pintype "passive"))
      (node (ref "S244") (pin "1") (pinfunction "1_1") (pintype "passive"))
      (node (ref "S258") (pin "2") (pinfunction "2_2") (pintype "passive"))
      (node (ref "S258_1") (pin "1") (pinfunction "1_1") (pintype "passive"))
    )
    (net (code "3") (name "/col3") (class "Default")
      (node (ref "S203") (pin "2") (pinfunction "2_2") (pintype "passive"))
      (node (ref "S217") (pin "2") (pinfunction "2_2") (pintype "passive"))
      (node (ref "S231") (pin "2") (pinfunction "2_2") (pintype "passive"))
      (node (ref "S245") (pin "2") (pinfunction "2_2") (pintype "passive"))
      (node (ref "S260") (pin "2") (pinfunction "2_2") (pintype "passive"))
      (node (ref "S260_1") (pin "1") (pinfunction "1_1") (pintype "passive"))
    )
    (net (code "4") (name "/col4") (class "Default")
      (node (ref "S204") (pin "2") (pinfunction "2_2") (pintype "passive"))
      (node (ref "S218") (pin "2") (pinfunction "2_2") (pintype "passive"))
      (node (ref "S232") (pin "2") (pinfunction "2_2") (pintype "passive"))
      (node (ref "S246") (pin "2") (pinfunction "2_2") (pintype "passive"))
    )
    (net (code "5") (name "/col5") (class "Default")
      (node (ref "S205") (pin "2") (pinfunction "2_2") (pintype "passive"))
      (node (ref "S219") (pin "2") (pinfunction "2_2") (pintype "passive"))
      (node (ref "S233") (pin "2") (pinfunction "2_2") (pintype "passive"))
      (node (ref "S247") (pin "2") (pinfunction "2_2") (pintype "passive"))
      (node (ref "S261") (pin "2") (pinfunction "2_2") (pintype "passive"))
      (node (ref "S261_1") (pin "2") (pinfunction "2_2") (pintype "passive"))
    )
    (net (code "6") (name "/col6") (class "Default")
      (node (ref "S206") (pin "2") (pinfunction "2_2") (pintype "passive"))
      (node (ref "S220") (pin "2") (pinfunction "2_2") (pintype "passive"))
      (node (ref "S234") (pin "2") (pinfunction "2_2") (pintype "passive"))
      (node (ref "S248") (pin "2") (pinfunction "2_2") (pintype "passive"))
    )
    (net (code "7") (name "/col7") (class "Default")
      (node (ref "S207") (pin "2") (pinfunction "2_2") (pintype "passive"))
      (node (ref "S221") (pin "2") (pinfunction "2_2") (pintype "passive"))
      (node (ref "S235") (pin "2") (pinfunction "2_2") (pintype "passive"))
      (node (ref "S249") (pin "2") (pinfunction "2_2") (pintype "passive"))
      (node (ref "S262") (pin "1") (pinfunction "1_1") (pintype "passive"))
      (node (ref "S262_1") (pin "1") (pinfunction "1_1") (pintype "passive"))
      (node (ref "S262_2") (pin "1") (pinfunction "1_1") (pintype "passive"))
    )
    (net (code "8") (name "/col8") (class "Default")
      (node (ref "S208") (pin "2") (pinfunction "2_2") (pintype "passive"))
      (node (ref "S222") (pin "2") (pinfunction "2_2") (pintype "passive"))
      (node (ref "S236") (pin "2") (pinfunction "2_2") (pintype "passive"))
      (node (ref "S250") (pin "2") (pinfunction "2_2") (pintype "passive"))
    )
    (net (code "9") (name "/col9") (class "Default")
      (node (ref "S209") (pin "2") (pinfunction "2_2") (pintype "passive"))
      (node (ref "S223") (pin "2") (pinfunction "2_2") (pintype "passive"))
      (node (ref "S237") (pin "2") (pinfunction "2_2") (pintype "passive"))
      (node (ref "S251") (pin "2") (pinfunction "2_2") (pintype "passive"))
      (node (ref "S263") (pin "1") (pinfunction "1_1") (pintype "passive"))
      (node (ref "S263_1") (pin "1") (pinfunction "1_1") (pintype "passive"))
    )
    (net (code "10") (name "/col10") (class "Default")
      (node (ref "S210") (pin "2") (pinfunction "2_2") (pintype "passive"))
      (node (ref "S224") (pin "2") (pinfunction "2_2") (pintype "passive"))
      (node (ref "S238") (pin "2") (pinfunction "2_2") (pintype "passive"))
      (node (ref "S252") (pin "2") (pinfunction "2_2") (pintype "passive"))
      (node (ref "S264") (pin "2") (pinfunction "2_2") (pintype "passive"))
    )
    (net (code "11") (name "/col11") (class "Default")
      (node (ref "S211") (pin "2") (pinfunction "2_2") (pintype "passive"))
      (node (ref "S225") (pin "2") (pinfunction "2_2") (pintype "passive"))
      (node (ref "S239") (pin "2") (pinfunction "2_2") (pintype "passive"))
      (node (ref "S253") (pin "2") (pinfunction "2_2") (pintype "passive"))
      (node (ref "S265") (pin "1") (pinfunction "1_1") (pintype "passive"))
      (node (ref "S265_1") (pin "1") (pinfunction "1_1") (pintype "passive"))
    )
    (net (code "12") (name "/col12") (class "Default")
      (node (ref "S212") (pin "2") (pinfunction "2_2") (pintype "passive"))
      (node (ref "S226") (pin "2") (pinfunction "2_2") (pintype "passive"))
      (node (ref "S240") (pin "2") (pinfunction "2_2") (pintype "passive"))
      (node (ref "S241") (pin "1") (pinfunction "1_1") (pintype "passive"))
      (node (ref "S241_1") (pin "1") (pinfunction "1_1") (pintype "passive"))
      (node (ref "S254") (pin "2") (pinfunction "2_2") (pintype "passive"))
    )
    (net (code "13") (name "/col13") (class "Default")
      (node (ref "S213") (pin "2") (pinfunction "2_2") (pintype "passive"))
      (node (ref "S227") (pin "2") (pinfunction "2_2") (pintype "passive"))
      (node (ref "S228_2") (pin "2") (pinfunction "2_2") (pintype "passive"))
      (node (ref "S256") (pin "2") (pinfunction "2_2") (pintype "passive"))
      (node (ref "S266") (pin "2") (pinfunction "2_2") (pintype "passive"))
      (node (ref "S266_1") (pin "2") (pinfunction "2_2") (pintype "passive"))
    )
    (net (code "14") (name "/col14") (class "Default")
      (node (ref "S214") (pin "2") (pinfunction "2_2") (pintype "passive"))
      (node (ref "S228") (pin "2") (pinfunction "2_2") (pintype "passive"))
      (node (ref "S242") (pin "2") (pinfunction "2_2") (pintype "passive"))
      (node (ref "S259") (pin "1") (pinfunction "1_1") (pintype "passive"))
      (node (ref "S259_1") (pin "2") (pinfunction "2_2") (pintype "passive"))
      (node (ref "S269") (pin "2") (pinfunction "2_2") (pintype "passive"))
    )
    (net (code "15") (name "/row1") (class "Default")
      (node (ref "D201") (pin "2") (pinfunction "K_2") (pintype "passive"))
      (node (ref "D202") (pin "2") (pinfunction "K_2") (pintype "passive"))
      (node (ref "D203") (pin "2") (pinfunction "K_2") (pintype "passive"))
      (node (ref "D204") (pin "2") (pinfunction "K_2") (pintype "passive"))
      (node (ref "D205") (pin "2") (pinfunction "K_2") (pintype "passive"))
      (node (ref "D206") (pin "2") (pinfunction "K_2") (pintype "passive"))
      (node (ref "D207") (pin "2") (pinfunction "K_2") (pintype "passive"))
      (node (ref "D208") (pin "2") (pinfunction "K_2") (pintype "passive"))
      (node (ref "D209") (pin "2") (pinfunction "K_2") (pintype "passive"))
      (node (ref "D210") (pin "2") (pinfunction "K_2") (pintype "passive"))
      (node (ref "D211") (pin "2") (pinfunction "K_2") (pintype "passive"))
      (node (ref "D212") (pin "2") (pinfunction "K_2") (pintype "passive"))
      (node (ref "D213") (pin "2") (pinfunction "K_2") (pintype "passive"))
      (node (ref "D214") (pin "2") (pinfunction "K_2") (pintype "passive"))
    )
    (net (code "16") (name "/row2") (class "Default")
      (node (ref "D215") (pin "2") (pinfunction "K_2") (pintype "passive"))
      (node (ref "D216") (pin "2") (pinfunction "K_2") (pintype "passive"))
      (node (ref "D217") (pin "2") (pinfunction "K_2") (pintype "passive"))
      (node (ref "D218") (pin "2") (pinfunction "K_2") (pintype "passive"))
      (node (ref "D219") (pin "2") (pinfunction "K_2") (pintype "passive"))
      (node (ref "D220") (pin "2") (pinfunction "K_2") (pintype "passive"))
      (node (ref "D221") (pin "2") (pinfunction "K_2") (pintype "passive"))
      (node (ref "D222") (pin "2") (pinfunction "K_2") (pintype "passive"))
      (node (ref "D223") (pin "2") (pinfunction "K_2") (pintype "passive"))
      (node (ref "D224") (pin "2") (pinfunction "K_2") (pintype "passive"))
      (node (ref "D225") (pin "2") (pinfunction "K_2") (pintype "passive"))
      (node (ref "D226") (pin "2") (pinfunction "K_2") (pintype "passive"))
      (node (ref "D227") (pin "2") (pinfunction "K_2") (pintype "passive"))
      (node (ref "D228") (pin "2") (pinfunction "K_2") (pintype "passive"))
    )
    (net (code "17") (name "/row3") (class "Default")
      (node (ref "D228_2") (pin "2") (pinfunction "K_2") (pintype "passive"))
      (node (ref "D229") (pin "2") (pinfunction "K_2") (pintype "passive"))
      (node (ref "D230") (pin "2") (pinfunction "K_2") (pintype "passive"))
      (node (ref "D231") (pin "2") (pinfunction "K_2") (pintype "passive"))
      (node (ref "D232") (pin "2") (pinfunction "K_2") (pintype "passive"))
      (node (ref "D233") (pin "2") (pinfunction "K_2") (pintype "passive"))
      (node (ref "D234") (pin "2") (pinfunction "K_2") (pintype "passive"))
      (node (ref "D235") (pin "2") (pinfunction "K_2") (pintype "passive"))
      (node (ref "D236") (pin "2") (pinfunction "K_2") (pintype "passive"))
      (node (ref "D237") (pin "2") (pinfunction "K_2") (pintype "passive"))
      (node (ref "D238") (pin "2") (pinfunction "K_2") (pintype "passive"))
      (node (ref "D239") (pin "2") (pinfunction "K_2") (pintype "passive"))
      (node (ref "D240") (pin "2") (pinfunction "K_2") (pintype "passive"))
      (node (ref "D259") (pin "2") (pinfunction "K_2") (pintype "passive"))
    )
    (net (code "18") (name "/row4") (class "Default")
      (node (ref "D242") (pin "2") (pinfunction "K_2") (pintype "passive"))
      (node (ref "D243") (pin "2") (pinfunction "K_2") (pintype "passive"))
      (node (ref "D244") (pin "2") (pinfunction "K_2") (pintype "passive"))
      (node (ref "D245") (pin "2") (pinfunction "K_2") (pintype "passive"))
      (node (ref "D246") (pin "2") (pinfunction "K_2") (pintype "passive"))
      (node (ref "D247") (pin "2") (pinfunction "K_2") (pintype "passive"))
      (node (ref "D248") (pin "2") (pinfunction "K_2") (pintype "passive"))
      (node (ref "D249") (pin "2") (pinfunction "K_2") (pintype "passive"))
      (node (ref "D250") (pin "2") (pinfunction "K_2") (pintype "passive"))
      (node (ref "D251") (pin "2") (pinfunction "K_2") (pintype "passive"))
      (node (ref "D252") (pin "2") (pinfunction "K_2") (pintype "passive"))
      (node (ref "D253") (pin "2") (pinfunction "K_2") (pintype "passive"))
      (node (ref "D254") (pin "2") (pinfunction "K_2") (pintype "passive"))
      (node (ref "D255") (pin "2") (pinfunction "K_2") (pintype "passive"))
    )
    (net (code "19") (name "/row5") (class "Default")
      (node (ref "D241") (pin "2") (pinfunction "K_2") (pintype "passive"))
      (node (ref "D256") (pin "2") (pinfunction "K_2") (pintype "passive"))
      (node (ref "D257") (pin "2") (pinfunction "K_2") (pintype "passive"))
      (node (ref "D258") (pin "2") (pinfunction "K_2") (pintype "passive"))
      (node (ref "D260") (pin "2") (pinfunction "K_2") (pintype "passive"))
      (node (ref "D261") (pin "2") (pinfunction "K_2") (pintype "passive"))
      (node (ref "D262") (pin "2") (pinfunction "K_2") (pintype "passive"))
      (node (ref "D263") (pin "2") (pinfunction "K_2") (pintype "passive"))
      (node (ref "D264") (pin "2") (pinfunction "K_2") (pintype "passive"))
      (node (ref "D265") (pin "2") (pinfunction "K_2") (pintype "passive"))
      (node (ref "D266") (pin "2") (pinfunction "K_2") (pintype "passive"))
    )
    (net (code "20") (name "Net-(D201-A)") (class "Default")
      (node (ref "D201") (pin "1") (pinfunction "A_1") (pintype "passive"))
      (node (ref "S201") (pin "1") (pinfunction "1_1") (pintype "passive"))
    )
    (net (code "21") (name "Net-(D202-A)") (class "Default")
      (node (ref "D202") (pin "1") (pinfunction "A_1") (pintype "passive"))
      (node (ref "S202") (pin "1") (pinfunction "1_1") (pintype "passive"))
    )
    (net (code "22") (name "Net-(D203-A)") (class "Default")
      (node (ref "D203") (pin "1") (pinfunction "A_1") (pintype "passive"))
      (node (ref "S203") (pin "1") (pinfunction "1_1") (pintype "passive"))
    )
    (net (code "23") (name "Net-(D204-A)") (class "Default")
      (node (ref "D204") (pin "1") (pinfunction "A_1") (pintype "passive"))
      (node (ref "S204") (pin "1") (pinfunction "1_1") (pintype "passive"))
    )
    (net (code "24") (name "Net-(D205-A)") (class "Default")
      (node (ref "D205") (pin "1") (pinfunction "A_1") (pintype "passive"))
      (node (ref "S205") (pin "1") (pinfunction "1_1") (pintype "passive"))
    )
    (net (code "25") (name "Net-(D206-A)") (class "Default")
      (node (ref "D206") (pin "1") (pinfunction "A_1") (pintype "passive"))
      (node (ref "S206") (pin "1") (pinfunction "1_1") (pintype "passive"))
    )
    (net (code "26") (name "Net-(D207-A)") (class "Default")
      (node (ref "D207") (pin "1") (pinfunction "A_1") (pintype "passive"))
      (node (ref "S207") (pin "1") (pinfunction "1_1") (pintype "passive"))
    )
    (net (code "27") (name "Net-(D208-A)") (class "Default")
      (node (ref "D208") (pin "1") (pinfunction "A_1") (pintype "passive"))
      (node (ref "S208") (pin "1") (pinfunction "1_1") (pintype "passive"))
    )
    (net (code "28") (name "Net-(D209-A)") (class "Default")
      (node (ref "D209") (pin "1") (pinfunction "A_1") (pintype "passive"))
      (node (ref "S209") (pin "1") (pinfunction "1_1") (pintype "passive"))
    )
    (net (code "29") (name "Net-(D210-A)") (class "Default")
      (node (ref "D210") (pin "1") (pinfunction "A_1") (pintype "passive"))
      (node (ref "S210") (pin "1") (pinfunction "1_1") (pintype "passive"))
    )
    (net (code "30") (name "Net-(D211-A)") (class "Default")
      (node (ref "D211") (pin "1") (pinfunction "A_1") (pintype "passive"))
      (node (ref "S211") (pin "1") (pinfunction "1_1") (pintype "passive"))
    )
    (net (code "31") (name "Net-(D212-A)") (class "Default")
      (node (ref "D212") (pin "1") (pinfunction "A_1") (pintype "passive"))
      (node (ref "S212") (pin "1") (pinfunction "1_1") (pintype "passive"))
    )
    (net (code "32") (name "Net-(D213-A)") (class "Default")
      (node (ref "D213") (pin "1") (pinfunction "A_1") (pintype "passive"))
      (node (ref "S213") (pin "1") (pinfunction "1_1") (pintype "passive"))
    )
    (net (code "33") (name "Net-(D214-A)") (class "Default")
      (node (ref "D214") (pin "1") (pinfunction "A_1") (pintype "passive"))
      (node (ref "S214") (pin "1") (pinfunction "1_1") (pintype "passive"))
    )
    (net (code "34") (name "Net-(D215-A)") (class "Default")
      (node (ref "D215") (pin "1") (pinfunction "A_1") (pintype "passive"))
      (node (ref "S215") (pin "1") (pinfunction "1_1") (pintype "passive"))
      (node (ref "S215_1") (pin "1") (pinfunction "1_1") (pintype "passive"))
    )
    (net (code "35") (name "Net-(D216-A)") (class "Default")
      (node (ref "D216") (pin "1") (pinfunction "A_1") (pintype "passive"))
      (node (ref "S216") (pin "1") (pinfunction "1_1") (pintype "passive"))
    )
    (net (code "36") (name "Net-(D217-A)") (class "Default")
      (node (ref "D217") (pin "1") (pinfunction "A_1") (pintype "passive"))
      (node (ref "S217") (pin "1") (pinfunction "1_1") (pintype "passive"))
    )
    (net (code "37") (name "Net-(D218-A)") (class "Default")
      (node (ref "D218") (pin "1") (pinfunction "A_1") (pintype "passive"))
      (node (ref "S218") (pin "1") (pinfunction "1_1") (pintype "passive"))
    )
    (net (code "38") (name "Net-(D219-A)") (class "Default")
      (node (ref "D219") (pin "1") (pinfunction "A_1") (pintype "passive"))
      (node (ref "S219") (pin "1") (pinfunction "1_1") (pintype "passive"))
    )
    (net (code "39") (name "Net-(D220-A)") (class "Default")
      (node (ref "D220") (pin "1") (pinfunction "A_1") (pintype "passive"))
      (node (ref "S220") (pin "1") (pinfunction "1_1") (pintype "passive"))
    )
    (net (code "40") (name "Net-(D221-A)") (class "Default")
      (node (ref "D221") (pin "1") (pinfunction "A_1") (pintype "passive"))
      (node (ref "S221") (pin "1") (pinfunction "1_1") (pintype "passive"))
    )
    (net (code "41") (name "Net-(D222-A)") (class "Default")
      (node (ref "D222") (pin "1") (pinfunction "A_1") (pintype "passive"))
      (node (ref "S222") (pin "1") (pinfunction "1_1") (pintype "passive"))
    )
    (net (code "42") (name "Net-(D223-A)") (class "Default")
      (node (ref "D223") (pin "1") (pinfunction "A_1") (pintype "passive"))
      (node (ref "S223") (pin "1") (pinfunction "1_1") (pintype "passive"))
    )
    (net (code "43") (name "Net-(D224-A)") (class "Default")
      (node (ref "D224") (pin "1") (pinfunction "A_1") (pintype "passive"))
      (node (ref "S224") (pin "1") (pinfunction "1_1") (pintype "passive"))
    )
    (net (code "44") (name "Net-(D225-A)") (class "Default")
      (node (ref "D225") (pin "1") (pinfunction "A_1") (pintype "passive"))
      (node (ref "S225") (pin "1") (pinfunction "1_1") (pintype "passive"))
    )
    (net (code "45") (name "Net-(D226-A)") (class "Default")
      (node (ref "D226") (pin "1") (pinfunction "A_1") (pintype "passive"))
      (node (ref "S226") (pin "1") (pinfunction "1_1") (pintype "passive"))
    )
    (net (code "46") (name "Net-(D227-A)") (class "Default")
      (node (ref "D227") (pin "1") (pinfunction "A_1") (pintype "passive"))
      (node (ref "S227") (pin "1") (pinfunction "1_1") (pintype "passive"))
    )
    (net (code "47") (name "Net-(D228-A)") (class "Default")
      (node (ref "D228") (pin "1") (pinfunction "A_1") (pintype "passive"))
      (node (ref "S228") (pin "1") (pinfunction "1_1") (pintype "passive"))
    )
    (net (code "48") (name "Net-(D228_2-A)") (class "Default")
      (node (ref "D228_2") (pin "1") (pinfunction "A_1") (pintype "passive"))
      (node (ref "S228_2") (pin "1") (pinfunction "1_1") (pintype "passive"))
    )
    (net (code "49") (name "Net-(D229-A)") (class "Default")
      (node (ref "D229") (pin "1") (pinfunction "A_1") (pintype "passive"))
      (node (ref "S229") (pin "2") (pinfunction "2_2") (pintype "passive"))
    )
    (net (code "50") (name "Net-(D230-A)") (class "Default")
      (node (ref "D230") (pin "1") (pinfunction "A_1") (pintype "passive"))
      (node (ref "S230") (pin "1") (pinfunction "1_1") (pintype "passive"))
    )
    (net (code "51") (name "Net-(D231-A)") (class "Default")
      (node (ref "D231") (pin "1") (pinfunction "A_1") (pintype "passive"))
      (node (ref "S231") (pin "1") (pinfunction "1_1") (pintype "passive"))
    )
    (net (code "52") (name "Net-(D232-A)") (class "Default")
      (node (ref "D232") (pin "1") (pinfunction "A_1") (pintype "passive"))
      (node (ref "S232") (pin "1") (pinfunction "1_1") (pintype "passive"))
    )
    (net (code "53") (name "Net-(D233-A)") (class "Default")
      (node (ref "D233") (pin "1") (pinfunction "A_1") (pintype "passive"))
      (node (ref "S233") (pin "1") (pinfunction "1_1") (pintype "passive"))
    )
    (net (code "54") (name "Net-(D234-A)") (class "Default")
      (node (ref "D234") (pin "1") (pinfunction "A_1") (pintype "passive"))
      (node (ref "S234") (pin "1") (pinfunction "1_1") (pintype "passive"))
    )
    (net (code "55") (name "Net-(D235-A)") (class "Default")
      (node (ref "D235") (pin "1") (pinfunction "A_1") (pintype "passive"))
      (node (ref "S235") (pin "1") (pinfunction "1_1") (pintype "passive"))
    )
    (net (code "56") (name "Net-(D236-A)") (class "Default")
      (node (ref "D236") (pin "1") (pinfunction "A_1") (pintype "passive"))
      (node (ref "S236") (pin "1") (pinfunction "1_1") (pintype "passive"))
    )
    (net (code "57") (name "Net-(D237-A)") (class "Default")
      (node (ref "D237") (pin "1") (pinfunction "A_1") (pintype "passive"))
      (node (ref "S237") (pin "1") (pinfunction "1_1") (pintype "passive"))
    )
    (net (code "58") (name "Net-(D238-A)") (class "Default")
      (node (ref "D238") (pin "1") (pinfunction "A_1") (pintype "passive"))
      (node (ref "S238") (pin "1") (pinfunction "1_1") (pintype "passive"))
    )
    (net (code "59") (name "Net-(D239-A)") (class "Default")
      (node (ref "D239") (pin "1") (pinfunction "A_1") (pintype "passive"))
      (node (ref "S239") (pin "1") (pinfunction "1_1") (pintype "passive"))
    )
    (net (code "60") (name "Net-(D240-A)") (class "Default")
      (node (ref "D240") (pin "1") (pinfunction "A_1") (pintype "passive"))
      (node (ref "S240") (pin "1") (pinfunction "1_1") (pintype "passive"))
    )
    (net (code "61") (name "Net-(D241-A)") (class "Default")
      (node (ref "D241") (pin "1") (pinfunction "A_1") (pintype "passive"))
      (node (ref "S241") (pin "2") (pinfunction "2_2") (pintype "passive"))
      (node (ref "S241_1") (pin "2") (pinfunction "2_2") (pintype "passive"))
    )
    (net (code "62") (name "Net-(D242-A)") (class "Default")
      (node (ref "D242") (pin "1") (pinfunction "A_1") (pintype "passive"))
      (node (ref "S242") (pin "1") (pinfunction "1_1") (pintype "passive"))
    )
    (net (code "63") (name "Net-(D243-A)") (class "Default")
      (node (ref "D243") (pin "1") (pinfunction "A_1") (pintype "passive"))
      (node (ref "S243") (pin "1") (pinfunction "1_1") (pintype "passive"))
      (node (ref "S243_1") (pin "1") (pinfunction "1_1") (pintype "passive"))
      (node (ref "S243_2") (pin "1") (pinfunction "1_1") (pintype "passive"))
      (node (ref "S243_3") (pin "1") (pinfunction "1_1") (pintype "passive"))
      (node (ref "S243_4") (pin "1") (pinfunction "1_1") (pintype "passive"))
    )
    (net (code "64") (name "Net-(D244-A)") (class "Default")
      (node (ref "D244") (pin "1") (pinfunction "A_1") (pintype "passive"))
      (node (ref "S244") (pin "2") (pinfunction "2_2") (pintype "passive"))
    )
    (net (code "65") (name "Net-(D245-A)") (class "Default")
      (node (ref "D245") (pin "1") (pinfunction "A_1") (pintype "passive"))
      (node (ref "S245") (pin "1") (pinfunction "1_1") (pintype "passive"))
    )
    (net (code "66") (name "Net-(D246-A)") (class "Default")
      (node (ref "D246") (pin "1") (pinfunction "A_1") (pintype "passive"))
      (node (ref "S246") (pin "1") (pinfunction "1_1") (pintype "passive"))
    )
    (net (code "67") (name "Net-(D247-A)") (class "Default")
      (node (ref "D247") (pin "1") (pinfunction "A_1") (pintype "passive"))
      (node (ref "S247") (pin "1") (pinfunction "1_1") (pintype "passive"))
    )
    (net (code "68") (name "Net-(D248-A)") (class "Default")
      (node (ref "D248") (pin "1") (pinfunction "A_1") (pintype "passive"))
      (node (ref "S248") (pin "1") (pinfunction "1_1") (pintype "passive"))
    )
    (net (code "69") (name "Net-(D249-A)") (class "Default")
      (node (ref "D249") (pin "1") (pinfunction "A_1") (pintype "passive"))
      (node (ref "S249") (pin "1") (pinfunction "1_1") (pintype "passive"))
    )
    (net (code "70") (name "Net-(D250-A)") (class "Default")
      (node (ref "D250") (pin "1") (pinfunction "A_1") (pintype "passive"))
      (node (ref "S250") (pin "1") (pinfunction "1_1") (pintype "passive"))
    )
    (net (code "71") (name "Net-(D251-A)") (class "Default")
      (node (ref "D251") (pin "1") (pinfunction "A_1") (pintype "passive"))
      (node (ref "S251") (pin "1") (pinfunction "1_1") (pintype "passive"))
    )
    (net (code "72") (name "Net-(D252-A)") (class "Default")
      (node (ref "D252") (pin "1") (pinfunction "A_1") (pintype "passive"))
      (node (ref "S252") (pin "1") (pinfunction "1_1") (pintype "passive"))
    )
    (net (code "73") (name "Net-(D253-A)") (class "Default")
      (node (ref "D253") (pin "1") (pinfunction "A_1") (pintype "passive"))
      (node (ref "S253") (pin "1") (pinfunction "1_1") (pintype "passive"))
    )
    (net (code "74") (name "Net-(D254-A)") (class "Default")
      (node (ref "D254") (pin "1") (pinfunction "A_1") (pintype "passive"))
      (node (ref "S254") (pin "1") (pinfunction "1_1") (pintype "passive"))
    )
    (net (code "75") (name "Net-(D255-A)") (class "Default")
      (node (ref "D255") (pin "1") (pinfunction "A_1") (pintype "passive"))
      (node (ref "S256") (pin "1") (pinfunction "1_1") (pintype "passive"))
    )
    (net (code "76") (name "Net-(D256-A)") (class "Default")
      (node (ref "D256") (pin "1") (pinfunction "A_1") (pintype "passive"))
      (node (ref "S269") (pin "1") (pinfunction "1_1") (pintype "passive"))
    )
    (net (code "77") (name "Net-(D257-A)") (class "Default")
      (node (ref "D257") (pin "1") (pinfunction "A_1") (pintype "passive"))
      (node (ref "S257") (pin "2") (pinfunction "2_2") (pintype "passive"))
      (node (ref "S257_1") (pin "2") (pinfunction "2_2") (pintype "passive"))
    )
    (net (code "78") (name "Net-(D258-A)") (class "Default")
      (node (ref "D258") (pin "1") (pinfunction "A_1") (pintype "passive"))
      (node (ref "S258") (pin "1") (pinfunction "1_1") (pintype "passive"))
      (node (ref "S258_1") (pin "2") (pinfunction "2_2") (pintype "passive"))
    )
    (net (code "79") (name "Net-(D259-A)") (class "Default")
      (node (ref "D259") (pin "1") (pinfunction "A_1") (pintype "passive"))
      (node (ref "S259") (pin "1") (pinfunction "1_1") (pintype "passive"))
      (node (ref "S259_1") (pin "1") (pinfunction "1_1") (pintype "passive"))
    )
    (net (code "80") (name "Net-(D260-A)") (class "Default")
      (node (ref "D260") (pin "1") (pinfunction "A_1") (pintype "passive"))
      (node (ref "S260") (pin "1") (pinfunction "1_1") (pintype "passive"))
      (node (ref "S260_1") (pin "2") (pinfunction "2_2") (pintype "passive"))
    )
    (net (code "81") (name "Net-(D261-A)") (class "Default")
      (node (ref "D261") (pin "1") (pinfunction "A_1") (pintype "passive"))
      (node (ref "S261") (pin "1") (pinfunction "1_1") (pintype "passive"))
      (node (ref "S261_1") (pin "1") (pinfunction "1_1") (pintype "passive"))
    )
    (net (code "82") (name "Net-(D262-A)") (class "Default")
      (node (ref "D262") (pin "1") (pinfunction "A_1") (pintype "passive"))
      (node (ref "S262") (pin "2") (pinfunction "2_2") (pintype "passive"))
      (node (ref "S262_1") (pin "2") (pinfunction "2_2") (pintype "passive"))
      (node (ref "S262_2") (pin "2") (pinfunction "2_2") (pintype "passive"))
    )
    (net (code "83") (name "Net-(D263-A)") (class "Default")
      (node (ref "D263") (pin "1") (pinfunction "A_1") (pintype "passive"))
      (node (ref "S263") (pin "2") (pinfunction "2_2") (pintype "passive"))
      (node (ref "S263_1") (pin "2") (pinfunction "2_2") (pintype "passive"))
    )
    (net (code "84") (name "Net-(D264-A)") (class "Default")
      (node (ref "D264") (pin "1") (pinfunction "A_1") (pintype "passive"))
      (node (ref "S264") (pin "1") (pinfunction "1_1") (pintype "passive"))
    )
    (net (code "85") (name "Net-(D265-A)") (class "Default")
      (node (ref "D265") (pin "1") (pinfunction "A_1") (pintype "passive"))
      (node (ref "S265") (pin "2") (pinfunction "2_2") (pintype "passive"))
      (node (ref "S265_1") (pin "2") (pinfunction "2_2") (pintype "passive"))
    )
    (net (code "86") (name "Net-(D266-A)") (class "Default")
      (node (ref "D266") (pin "1") (pinfunction "A_1") (pintype "passive"))
      (node (ref "S266") (pin "1") (pinfunction "1_1") (pintype "passive"))
      (node (ref "S266_1") (pin "1") (pinfunction "1_1") (pintype "passive"))
    )
    (net (code "87") (name "unconnected-(STAB1-Pad1)") (class "Default")
      (node (ref "STAB1") (pin "1") (pinfunction "1_1") (pintype "passive"))
    )
  )
)
